# 06-Key.net
KiCad netlist of a schematic drawn in Altium Designer
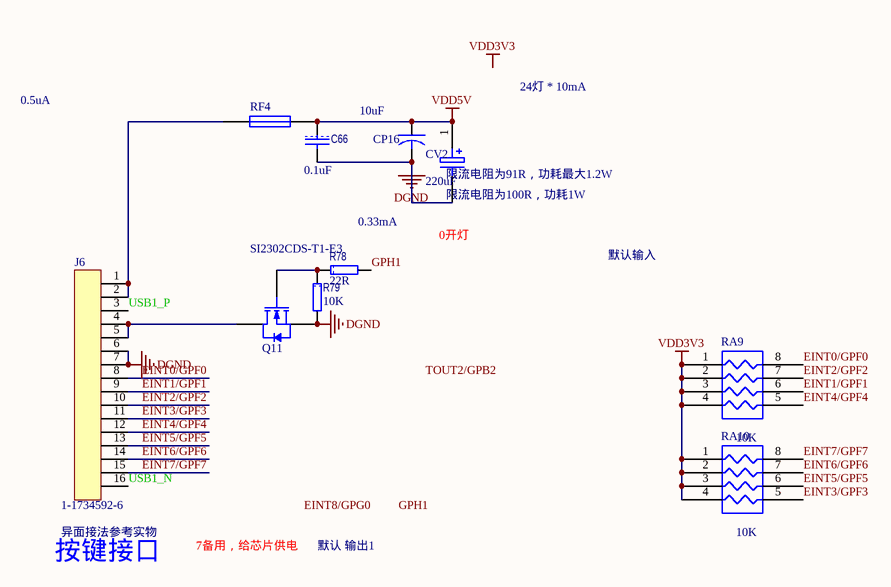
[diagram p0: 06-Key.SchDoc]

(export (version "E")
  (design (tool "Eeschema 10.0.6"))
  (components
    (comp (ref "C66")
      (value "0.1uF")
      (footprint "1608[0603]C")
      (description "多层陶瓷电容器MLCC - SMD/SMT 0603 0.1uF 50volts X7R 10%")
      (fields (field (name "MANUFACTURER") "TDK") (field (name "MANUFACTURER PART NUMBER") "C1608X7R1H104K"))
      (libsource (lib "*") (part "CAP"))
    )
    (comp (ref "CP16")
      (value "10uF")
      (footprint "3216[1206]CB")
      (description "钽质电容器-固体SMD 16volts 10uF 10%")
      (fields (field (name "MANUFACTURER") "AVX") (field (name "MANUFACTURER PART NUMBER") "TAJA106K016RNJ"))
      (libsource (lib "*") (part "CAPACITOR"))
    )
    (comp (ref "CV2")
      (value "220uF")
      (footprint "CAPPR5-10x20/H1.1")
      (description "插针 铝质电解电容器 - 带引线 220UF 35V ELECT FM RADIAL")
      (fields
        (field (name "MANUFACTURER") "Panasonic Electronic Components")
        (field (name "MANUFACTURER PART NUMBER") "EEU-FM1V471")
      )
      (libsource (lib "*") (part "ELECTRO1"))
    )
    (comp (ref "J6")
      (value "1-1734592-6")
      (footprint "FFC/SM0.5-2H16")
      (description "TE CONNECTIVITY / AMP - 1-1734592-6 - FFC/FPC CONNECTOR, RECEPTACLE 16POS 1ROW")
      (fields (field (name "MANUFACTURER") "TE CONNECTIVITY / AMP"))
      (libsource (lib "*") (part "16PIN"))
    )
    (comp (ref "Q11")
      (value "SI2302CDS-T1-E3")
      (footprint "SOT23_N")
      (description "MOSFET 20V 2.9A 0.86W 57mohm @ 4.5V")
      (fields (field (name "MANUFACTURER") "Vishay / Siliconix"))
      (libsource (lib "Philips Discrete MOSFET - Low Power") (part "2N7002"))
    )
    (comp (ref "R78")
      (value "22R")
      (footprint "1608[0603]R")
      (description "厚膜电阻器 - SMD 1/10watt 22ohms 1%")
      (fields
        (field (name "MANUFACTURER") "Vishay / Dale")
        (field (name "MANUFACTURER PART NUMBER") "CRCW060322R0FKEA")
      )
      (libsource (lib "22R 1%") (part "RES"))
    )
    (comp (ref "R79")
      (value "10K")
      (footprint "1608[0603]R")
      (description "厚膜电阻器 - SMD 1/10watt 10Kohms 1%")
      (fields
        (field (name "MANUFACTURER") "Vishay / Dale")
        (field (name "MANUFACTURER PART NUMBER") "CRCW060310K0FKEA")
      )
      (libsource (lib "10K 1%") (part "RES"))
    )
    (comp (ref "RA9")
      (value "10K")
      (footprint "R-AR4")
      (description "电阻器网络与阵列 8Term 10Kohms 5% Convex")
      (fields
        (field (name "MANUFACTURER") "Vishay / Dale")
        (field (name "MANUFACTURER PART NUMBER") "CRA06S08310K0JTA")
      )
      (libsource (lib "*") (part "RP4R"))
    )
    (comp (ref "RA10")
      (value "10K")
      (footprint "R-AR4")
      (description "电阻器网络与阵列 8Term 10Kohms 5% Convex")
      (fields
        (field (name "MANUFACTURER") "Vishay / Dale")
        (field (name "MANUFACTURER PART NUMBER") "CRA06S08310K0JTA")
      )
      (libsource (lib "*") (part "RP4R"))
    )
    (comp (ref "RF4")
      (value "0805L050WR")
      (footprint "2012[0805]F")
      (description "可复位保险丝 PTC 30V POLY SURF MOUNT 0805.500A")
      (fields (field (name "MANUFACTURER") "Littelfuse"))
      (libsource (lib "*") (part "FUSE1"))
    )
  )
  (nets
    (net (code "1") (name "/EINT0{slash}GPF0") (class "Default")
      (node (ref "J6") (pin "8") (pinfunction "8_8") (pintype "passive"))
      (node (ref "RA9") (pin "8") (pinfunction "R1_8") (pintype "passive"))
    )
    (net (code "2") (name "/EINT1{slash}GPF1") (class "Default")
      (node (ref "J6") (pin "9") (pinfunction "9_9") (pintype "passive"))
      (node (ref "RA9") (pin "6") (pinfunction "R3_6") (pintype "passive"))
    )
    (net (code "3") (name "/EINT2{slash}GPF2") (class "Default")
      (node (ref "J6") (pin "10") (pinfunction "10_10") (pintype "passive"))
      (node (ref "RA9") (pin "7") (pinfunction "R2_7") (pintype "passive"))
    )
    (net (code "4") (name "/EINT3{slash}GPF3") (class "Default")
      (node (ref "J6") (pin "11") (pinfunction "11_11") (pintype "passive"))
      (node (ref "RA10") (pin "5") (pinfunction "R4_5") (pintype "passive"))
    )
    (net (code "5") (name "/EINT4{slash}GPF4") (class "Default")
      (node (ref "J6") (pin "12") (pinfunction "12_12") (pintype "passive"))
      (node (ref "RA9") (pin "5") (pinfunction "R4_5") (pintype "passive"))
    )
    (net (code "6") (name "/EINT5{slash}GPF5") (class "Default")
      (node (ref "J6") (pin "13") (pinfunction "13_13") (pintype "passive"))
      (node (ref "RA10") (pin "6") (pinfunction "R3_6") (pintype "passive"))
    )
    (net (code "7") (name "/EINT6{slash}GPF6") (class "Default")
      (node (ref "J6") (pin "14") (pinfunction "14_14") (pintype "passive"))
      (node (ref "RA10") (pin "7") (pinfunction "R2_7") (pintype "passive"))
    )
    (net (code "8") (name "/EINT7{slash}GPF7") (class "Default")
      (node (ref "J6") (pin "15") (pinfunction "15_15") (pintype "passive"))
      (node (ref "RA10") (pin "8") (pinfunction "R1_8") (pintype "passive"))
    )
    (net (code "10") (name "/GPH1") (class "Default")
      (node (ref "R78") (pin "2") (pinfunction "2_2") (pintype "passive"))
    )
    (net (code "12") (name "/USB1_N") (class "Default")
      (node (ref "J6") (pin "16") (pinfunction "16_16") (pintype "passive"))
    )
    (net (code "13") (name "/USB1_P") (class "Default")
      (node (ref "J6") (pin "3") (pinfunction "3_3") (pintype "passive"))
    )
    (net (code "14") (name "DGND") (class "Default")
      (node (ref "C66") (pin "2") (pinfunction "2_2") (pintype "passive"))
      (node (ref "CP16") (pin "2") (pinfunction "2_2") (pintype "passive"))
      (node (ref "CV2") (pin "2") (pinfunction "2_2") (pintype "passive"))
      (node (ref "J6") (pin "6") (pinfunction "6_6") (pintype "passive"))
      (node (ref "J6") (pin "7") (pinfunction "7_7") (pintype "passive"))
      (node (ref "Q11") (pin "2") (pinfunction "S_2") (pintype "passive"))
      (node (ref "R79") (pin "2") (pinfunction "2_2") (pintype "passive"))
    )
    (net (code "15") (name "Net-(J6-Pad1)") (class "Default")
      (node (ref "J6") (pin "1") (pinfunction "1_1") (pintype "passive"))
      (node (ref "J6") (pin "2") (pinfunction "2_2") (pintype "passive"))
      (node (ref "RF4") (pin "1") (pinfunction "1_1") (pintype "passive"))
    )
    (net (code "16") (name "Net-(Q11-D)") (class "Default")
      (node (ref "J6") (pin "4") (pinfunction "4_4") (pintype "passive"))
      (node (ref "J6") (pin "5") (pinfunction "5_5") (pintype "passive"))
      (node (ref "Q11") (pin "3") (pinfunction "D_3") (pintype "passive"))
    )
    (net (code "17") (name "Net-(Q11-G)") (class "Default")
      (node (ref "Q11") (pin "1") (pinfunction "G_1") (pintype "passive"))
      (node (ref "R78") (pin "1") (pinfunction "1_1") (pintype "passive"))
      (node (ref "R79") (pin "1") (pinfunction "1_1") (pintype "passive"))
    )
    (net (code "18") (name "VDD3V3") (class "Default")
      (node (ref "RA10") (pin "1") (pinfunction "R1_1") (pintype "passive"))
      (node (ref "RA10") (pin "2") (pinfunction "R2_2") (pintype "passive"))
      (node (ref "RA10") (pin "3") (pinfunction "R3_3") (pintype "passive"))
      (node (ref "RA10") (pin "4") (pinfunction "R4_4") (pintype "passive"))
      (node (ref "RA9") (pin "1") (pinfunction "R1_1") (pintype "passive"))
      (node (ref "RA9") (pin "2") (pinfunction "R2_2") (pintype "passive"))
      (node (ref "RA9") (pin "3") (pinfunction "R3_3") (pintype "passive"))
      (node (ref "RA9") (pin "4") (pinfunction "R4_4") (pintype "passive"))
    )
    (net (code "19") (name "VDD5V") (class "Default")
      (node (ref "C66") (pin "1") (pinfunction "1_1") (pintype "passive"))
      (node (ref "CP16") (pin "1") (pinfunction "1_1") (pintype "passive"))
      (node (ref "CV2") (pin "1") (pinfunction "1_1") (pintype "passive"))
      (node (ref "RF4") (pin "2") (pinfunction "2_2") (pintype "passive"))
    )
  )
)
